# ESRMeter.net
KiCad netlist of a schematic drawn in EAGLE
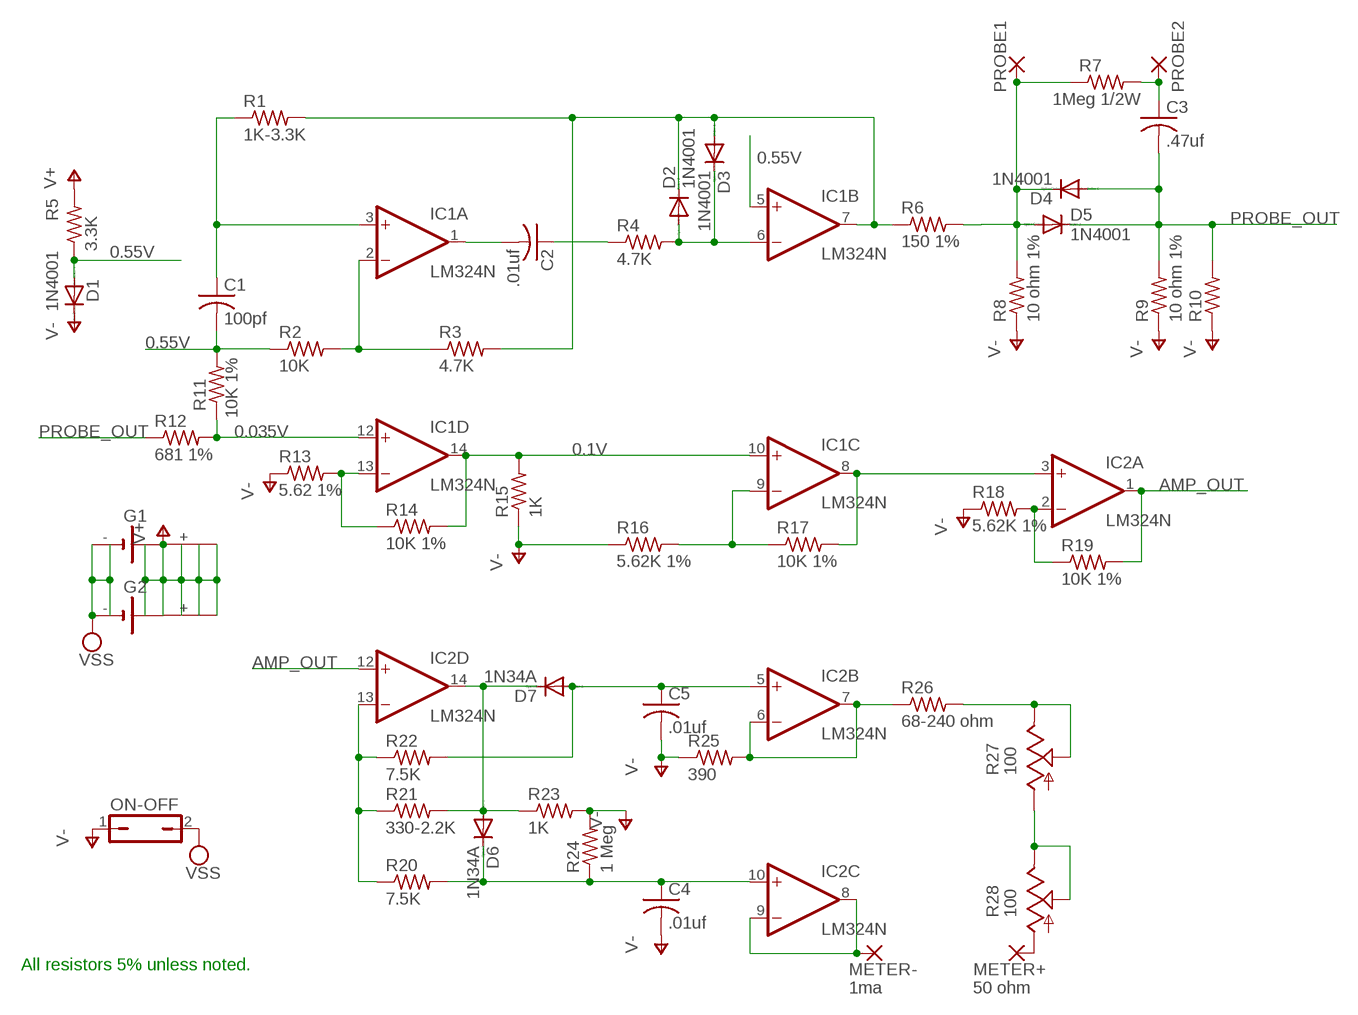
[diagram p0: schematic, sheet 1]

(export (version "E")
  (design (tool "Eeschema 10.0.6"))
  (components
    (comp (ref "C1")
      (value "100pf")
      (footprint "eagle-import:C050-025X075")
      (libsource (lib "eagle-import") (part "C-US050-025X075"))
    )
    (comp (ref "C2")
      (value ".01uf")
      (footprint "eagle-import:C050-025X075")
      (libsource (lib "eagle-import") (part "C-US050-025X075"))
    )
    (comp (ref "C3")
      (value ".47uf")
      (footprint "eagle-import:C075-052X106")
      (libsource (lib "eagle-import") (part "C-US075-052X106"))
    )
    (comp (ref "C4")
      (value ".01uf")
      (footprint "eagle-import:C050-025X075")
      (libsource (lib "eagle-import") (part "C-US050-025X075"))
    )
    (comp (ref "C5")
      (value ".01uf")
      (footprint "eagle-import:C050-025X075")
      (libsource (lib "eagle-import") (part "C-US050-025X075"))
    )
    (comp (ref "D1")
      (value "1N4001")
      (footprint "eagle-import:DO41-10")
      (libsource (lib "eagle-import") (part "1N4004"))
    )
    (comp (ref "D2")
      (value "1N4001")
      (footprint "eagle-import:DO41-10")
      (libsource (lib "eagle-import") (part "1N4004"))
    )
    (comp (ref "D3")
      (value "1N4001")
      (footprint "eagle-import:DO41-10")
      (libsource (lib "eagle-import") (part "1N4004"))
    )
    (comp (ref "D4")
      (value "1N4001")
      (footprint "eagle-import:DO41-10")
      (libsource (lib "eagle-import") (part "1N4004"))
    )
    (comp (ref "D5")
      (value "1N4001")
      (footprint "eagle-import:DO41-10")
      (libsource (lib "eagle-import") (part "1N4004"))
    )
    (comp (ref "D6")
      (value "1N34A")
      (footprint "eagle-import:DO41-10")
      (libsource (lib "eagle-import") (part "1N4004"))
    )
    (comp (ref "D7")
      (value "1N34A")
      (footprint "eagle-import:DO41-10")
      (libsource (lib "eagle-import") (part "1N4004"))
    )
    (comp (ref "G1")
      (value "B2430UNI")
      (footprint "eagle-import:B2430UNI")
      (libsource (lib "eagle-import") (part "B2430UNI"))
    )
    (comp (ref "G2")
      (value "B2430UNI")
      (footprint "eagle-import:B2430UNI")
      (libsource (lib "eagle-import") (part "B2430UNI"))
    )
    (comp (ref "IC1")
      (value "LM324N")
      (footprint "eagle-import:DIL14")
      (libsource (lib "eagle-import") (part "LM324N"))
    )
    (comp (ref "IC2")
      (value "LM324N")
      (footprint "eagle-import:DIL14")
      (libsource (lib "eagle-import") (part "LM324N"))
    )
    (comp (ref "METER+")
      (value "50 ohm")
      (footprint "eagle-import:2,15_1,0")
      (libsource (lib "eagle-import") (part "2,15/1,0"))
    )
    (comp (ref "METER-")
      (value "1ma")
      (footprint "eagle-import:2,15_1,0")
      (libsource (lib "eagle-import") (part "2,15/1,0"))
    )
    (comp (ref "ON-OFF")
      (value "JP1Q")
      (footprint "eagle-import:JP1")
      (libsource (lib "eagle-import") (part "JP1Q"))
    )
    (comp (ref "PROBE1")
      (value "2,15/1,0")
      (footprint "eagle-import:2,15_1,0")
      (libsource (lib "eagle-import") (part "2,15/1,0"))
    )
    (comp (ref "PROBE2")
      (value "2,15/1,0")
      (footprint "eagle-import:2,15_1,0")
      (libsource (lib "eagle-import") (part "2,15/1,0"))
    )
    (comp (ref "R1")
      (value "1K-3.3K")
      (footprint "eagle-import:0207_10")
      (libsource (lib "eagle-import") (part "R-US_0207/10"))
    )
    (comp (ref "R2")
      (value "10K")
      (footprint "eagle-import:0207_10")
      (libsource (lib "eagle-import") (part "R-US_0207/10"))
    )
    (comp (ref "R3")
      (value "4.7K")
      (footprint "eagle-import:0207_10")
      (libsource (lib "eagle-import") (part "R-US_0207/10"))
    )
    (comp (ref "R4")
      (value "4.7K")
      (footprint "eagle-import:0207_10")
      (libsource (lib "eagle-import") (part "R-US_0207/10"))
    )
    (comp (ref "R5")
      (value "3.3K")
      (footprint "eagle-import:0207_10")
      (libsource (lib "eagle-import") (part "R-US_0207/10"))
    )
    (comp (ref "R6")
      (value "150 1%")
      (footprint "eagle-import:0207_10")
      (libsource (lib "eagle-import") (part "R-US_0207/10"))
    )
    (comp (ref "R7")
      (value "1Meg 1/2W")
      (footprint "eagle-import:0207_12")
      (libsource (lib "eagle-import") (part "R-US_0207/12"))
    )
    (comp (ref "R8")
      (value "10 ohm 1%")
      (footprint "eagle-import:0207_10")
      (libsource (lib "eagle-import") (part "R-US_0207/10"))
    )
    (comp (ref "R9")
      (value "10 ohm 1%")
      (footprint "eagle-import:0207_10")
      (libsource (lib "eagle-import") (part "R-US_0207/10"))
    )
    (comp (ref "R10")
      (value "R-US_0207/10")
      (footprint "eagle-import:0207_10")
      (libsource (lib "eagle-import") (part "R-US_0207/10"))
    )
    (comp (ref "R11")
      (value "10K 1%")
      (footprint "eagle-import:0207_10")
      (libsource (lib "eagle-import") (part "R-US_0207/10"))
    )
    (comp (ref "R12")
      (value "681 1%")
      (footprint "eagle-import:0207_10")
      (libsource (lib "eagle-import") (part "R-US_0207/10"))
    )
    (comp (ref "R13")
      (value "5.62 1%")
      (footprint "eagle-import:0207_10")
      (libsource (lib "eagle-import") (part "R-US_0207/10"))
    )
    (comp (ref "R14")
      (value "10K 1%")
      (footprint "eagle-import:0207_10")
      (libsource (lib "eagle-import") (part "R-US_0207/10"))
    )
    (comp (ref "R15")
      (value "1K")
      (footprint "eagle-import:0207_10")
      (libsource (lib "eagle-import") (part "R-US_0207/10"))
    )
    (comp (ref "R16")
      (value "5.62K 1%")
      (footprint "eagle-import:0207_10")
      (libsource (lib "eagle-import") (part "R-US_0207/10"))
    )
    (comp (ref "R17")
      (value "10K 1%")
      (footprint "eagle-import:0207_10")
      (libsource (lib "eagle-import") (part "R-US_0207/10"))
    )
    (comp (ref "R18")
      (value "5.62K 1%")
      (footprint "eagle-import:0207_10")
      (libsource (lib "eagle-import") (part "R-US_0207/10"))
    )
    (comp (ref "R19")
      (value "10K 1%")
      (footprint "eagle-import:0207_10")
      (libsource (lib "eagle-import") (part "R-US_0207/10"))
    )
    (comp (ref "R20")
      (value "7.5K")
      (footprint "eagle-import:0207_10")
      (libsource (lib "eagle-import") (part "R-US_0207/10"))
    )
    (comp (ref "R21")
      (value "330-2.2K")
      (footprint "eagle-import:0207_10")
      (libsource (lib "eagle-import") (part "R-US_0207/10"))
    )
    (comp (ref "R22")
      (value "7.5K")
      (footprint "eagle-import:0207_10")
      (libsource (lib "eagle-import") (part "R-US_0207/10"))
    )
    (comp (ref "R23")
      (value "1K")
      (footprint "eagle-import:0207_10")
      (libsource (lib "eagle-import") (part "R-US_0207/10"))
    )
    (comp (ref "R24")
      (value "1 Meg")
      (footprint "eagle-import:0207_12")
      (libsource (lib "eagle-import") (part "R-US_0207/12"))
    )
    (comp (ref "R25")
      (value "390")
      (footprint "eagle-import:0207_10")
      (libsource (lib "eagle-import") (part "R-US_0207/10"))
    )
    (comp (ref "R26")
      (value "68-240 ohm")
      (footprint "eagle-import:0207_10")
      (libsource (lib "eagle-import") (part "R-US_0207/10"))
    )
    (comp (ref "R27")
      (value "100")
      (footprint "eagle-import:B64W")
      (libsource (lib "eagle-import") (part "TRIM_US-B64W"))
    )
    (comp (ref "R28")
      (value "100")
      (footprint "eagle-import:B64W")
      (libsource (lib "eagle-import") (part "TRIM_US-B64W"))
    )
  )
  (nets
    (net (code "1") (name "/0.1V") (class "Default")
      (node (ref "IC1") (pin "10") (pinfunction "+IN_10") (pintype "input"))
      (node (ref "IC1") (pin "14") (pinfunction "OUT_14") (pintype "output"))
      (node (ref "R14") (pin "2") (pinfunction "2_2") (pintype "passive"))
      (node (ref "R15") (pin "2") (pinfunction "2_2") (pintype "passive"))
    )
    (net (code "2") (name "/0.035V") (class "Default")
      (node (ref "IC1") (pin "12") (pinfunction "+IN_12") (pintype "input"))
      (node (ref "R11") (pin "1") (pinfunction "1_1") (pintype "passive"))
      (node (ref "R12") (pin "2") (pinfunction "2_2") (pintype "passive"))
    )
    (net (code "3") (name "/0.55V") (class "Default")
      (node (ref "C1") (pin "2") (pinfunction "2_2") (pintype "passive"))
      (node (ref "D1") (pin "A") (pinfunction "A_A") (pintype "passive"))
      (node (ref "IC1") (pin "5") (pinfunction "+IN_5") (pintype "input"))
      (node (ref "R11") (pin "2") (pinfunction "2_2") (pintype "passive"))
      (node (ref "R2") (pin "1") (pinfunction "1_1") (pintype "passive"))
      (node (ref "R5") (pin "1") (pinfunction "1_1") (pintype "passive"))
    )
    (net (code "4") (name "/AMP_OUT") (class "Default")
      (node (ref "IC2") (pin "1") (pinfunction "OUT_1") (pintype "output"))
      (node (ref "IC2") (pin "12") (pinfunction "+IN_12") (pintype "input"))
      (node (ref "R19") (pin "2") (pinfunction "2_2") (pintype "passive"))
    )
    (net (code "5") (name "/PROBE_OUT") (class "Default")
      (node (ref "C3") (pin "2") (pinfunction "2_2") (pintype "passive"))
      (node (ref "D4") (pin "A") (pinfunction "A_A") (pintype "passive"))
      (node (ref "D5") (pin "C") (pinfunction "C_C") (pintype "passive"))
      (node (ref "R10") (pin "2") (pinfunction "2_2") (pintype "passive"))
      (node (ref "R12") (pin "1") (pinfunction "1_1") (pintype "passive"))
      (node (ref "R9") (pin "2") (pinfunction "2_2") (pintype "passive"))
    )
    (net (code "6") (name "Net-(C2-Pad1)") (class "Default")
      (node (ref "C2") (pin "1") (pinfunction "1_1") (pintype "passive"))
      (node (ref "R4") (pin "1") (pinfunction "1_1") (pintype "passive"))
    )
    (net (code "7") (name "Net-(IC1A-+IN)") (class "Default")
      (node (ref "C1") (pin "1") (pinfunction "1_1") (pintype "passive"))
      (node (ref "IC1") (pin "3") (pinfunction "+IN_3") (pintype "input"))
      (node (ref "R1") (pin "1") (pinfunction "1_1") (pintype "passive"))
    )
    (net (code "8") (name "Net-(IC1A--IN)") (class "Default")
      (node (ref "IC1") (pin "2") (pinfunction "-IN_2") (pintype "input"))
      (node (ref "R2") (pin "2") (pinfunction "2_2") (pintype "passive"))
      (node (ref "R3") (pin "1") (pinfunction "1_1") (pintype "passive"))
    )
    (net (code "9") (name "Net-(IC1A-OUT)") (class "Default")
      (node (ref "C2") (pin "2") (pinfunction "2_2") (pintype "passive"))
      (node (ref "IC1") (pin "1") (pinfunction "OUT_1") (pintype "output"))
    )
    (net (code "10") (name "Net-(IC1B--IN)") (class "Default")
      (node (ref "D2") (pin "A") (pinfunction "A_A") (pintype "passive"))
      (node (ref "D3") (pin "C") (pinfunction "C_C") (pintype "passive"))
      (node (ref "IC1") (pin "6") (pinfunction "-IN_6") (pintype "input"))
      (node (ref "R4") (pin "2") (pinfunction "2_2") (pintype "passive"))
    )
    (net (code "11") (name "Net-(IC1B-OUT)") (class "Default")
      (node (ref "D2") (pin "C") (pinfunction "C_C") (pintype "passive"))
      (node (ref "D3") (pin "A") (pinfunction "A_A") (pintype "passive"))
      (node (ref "IC1") (pin "7") (pinfunction "OUT_7") (pintype "output"))
      (node (ref "R1") (pin "2") (pinfunction "2_2") (pintype "passive"))
      (node (ref "R3") (pin "2") (pinfunction "2_2") (pintype "passive"))
      (node (ref "R6") (pin "1") (pinfunction "1_1") (pintype "passive"))
    )
    (net (code "12") (name "Net-(IC1C--IN)") (class "Default")
      (node (ref "IC1") (pin "9") (pinfunction "-IN_9") (pintype "input"))
      (node (ref "R16") (pin "2") (pinfunction "2_2") (pintype "passive"))
      (node (ref "R17") (pin "1") (pinfunction "1_1") (pintype "passive"))
    )
    (net (code "13") (name "Net-(IC1C-OUT)") (class "Default")
      (node (ref "IC1") (pin "8") (pinfunction "OUT_8") (pintype "output"))
      (node (ref "IC2") (pin "3") (pinfunction "+IN_3") (pintype "input"))
      (node (ref "R17") (pin "2") (pinfunction "2_2") (pintype "passive"))
    )
    (net (code "14") (name "Net-(IC1D--IN)") (class "Default")
      (node (ref "IC1") (pin "13") (pinfunction "-IN_13") (pintype "input"))
      (node (ref "R13") (pin "2") (pinfunction "2_2") (pintype "passive"))
      (node (ref "R14") (pin "1") (pinfunction "1_1") (pintype "passive"))
    )
    (net (code "15") (name "Net-(IC2A--IN)") (class "Default")
      (node (ref "IC2") (pin "2") (pinfunction "-IN_2") (pintype "input"))
      (node (ref "R18") (pin "2") (pinfunction "2_2") (pintype "passive"))
      (node (ref "R19") (pin "1") (pinfunction "1_1") (pintype "passive"))
    )
    (net (code "16") (name "Net-(IC2B-+IN)") (class "Default")
      (node (ref "C5") (pin "1") (pinfunction "1_1") (pintype "passive"))
      (node (ref "D7") (pin "A") (pinfunction "A_A") (pintype "passive"))
      (node (ref "IC2") (pin "5") (pinfunction "+IN_5") (pintype "input"))
      (node (ref "R22") (pin "2") (pinfunction "2_2") (pintype "passive"))
    )
    (net (code "17") (name "Net-(IC2B--IN)") (class "Default")
      (node (ref "IC2") (pin "6") (pinfunction "-IN_6") (pintype "input"))
      (node (ref "IC2") (pin "7") (pinfunction "OUT_7") (pintype "output"))
      (node (ref "R25") (pin "2") (pinfunction "2_2") (pintype "passive"))
      (node (ref "R26") (pin "1") (pinfunction "1_1") (pintype "passive"))
    )
    (net (code "18") (name "Net-(IC2C-+IN)") (class "Default")
      (node (ref "C4") (pin "1") (pinfunction "1_1") (pintype "passive"))
      (node (ref "D6") (pin "C") (pinfunction "C_C") (pintype "passive"))
      (node (ref "IC2") (pin "10") (pinfunction "+IN_10") (pintype "input"))
      (node (ref "R20") (pin "2") (pinfunction "2_2") (pintype "passive"))
      (node (ref "R24") (pin "1") (pinfunction "1_1") (pintype "passive"))
    )
    (net (code "19") (name "Net-(IC2C--IN)") (class "Default")
      (node (ref "IC2") (pin "8") (pinfunction "OUT_8") (pintype "output"))
      (node (ref "IC2") (pin "9") (pinfunction "-IN_9") (pintype "input"))
      (node (ref "METER-") (pin "1") (pinfunction "P_1") (pintype "passive"))
    )
    (net (code "20") (name "Net-(IC2D--IN)") (class "Default")
      (node (ref "IC2") (pin "13") (pinfunction "-IN_13") (pintype "input"))
      (node (ref "R20") (pin "1") (pinfunction "1_1") (pintype "passive"))
      (node (ref "R21") (pin "1") (pinfunction "1_1") (pintype "passive"))
      (node (ref "R22") (pin "1") (pinfunction "1_1") (pintype "passive"))
    )
    (net (code "21") (name "Net-(IC2D-OUT)") (class "Default")
      (node (ref "D6") (pin "A") (pinfunction "A_A") (pintype "passive"))
      (node (ref "D7") (pin "C") (pinfunction "C_C") (pintype "passive"))
      (node (ref "IC2") (pin "14") (pinfunction "OUT_14") (pintype "output"))
      (node (ref "R21") (pin "2") (pinfunction "2_2") (pintype "passive"))
      (node (ref "R23") (pin "1") (pinfunction "1_1") (pintype "passive"))
    )
    (net (code "22") (name "Net-(METER+-P)") (class "Default")
      (node (ref "METER+") (pin "1") (pinfunction "P_1") (pintype "passive"))
      (node (ref "R28") (pin "A") (pinfunction "A_A") (pintype "passive"))
    )
    (net (code "23") (name "Net-(PROBE1-P)") (class "Default")
      (node (ref "D4") (pin "C") (pinfunction "C_C") (pintype "passive"))
      (node (ref "D5") (pin "A") (pinfunction "A_A") (pintype "passive"))
      (node (ref "PROBE1") (pin "1") (pinfunction "P_1") (pintype "passive"))
      (node (ref "R6") (pin "2") (pinfunction "2_2") (pintype "passive"))
      (node (ref "R7") (pin "1") (pinfunction "1_1") (pintype "passive"))
      (node (ref "R8") (pin "2") (pinfunction "2_2") (pintype "passive"))
    )
    (net (code "24") (name "Net-(PROBE2-P)") (class "Default")
      (node (ref "C3") (pin "1") (pinfunction "1_1") (pintype "passive"))
      (node (ref "PROBE2") (pin "1") (pinfunction "P_1") (pintype "passive"))
      (node (ref "R7") (pin "2") (pinfunction "2_2") (pintype "passive"))
    )
    (net (code "25") (name "Net-(R26-Pad2)") (class "Default")
      (node (ref "R26") (pin "2") (pinfunction "2_2") (pintype "passive"))
      (node (ref "R27") (pin "E") (pinfunction "E_E") (pintype "passive"))
      (node (ref "R27") (pin "S") (pinfunction "S_S") (pintype "passive"))
    )
    (net (code "26") (name "Net-(R27-PadA)") (class "Default")
      (node (ref "R27") (pin "A") (pinfunction "A_A") (pintype "passive"))
      (node (ref "R28") (pin "E") (pinfunction "E_E") (pintype "passive"))
      (node (ref "R28") (pin "S") (pinfunction "S_S") (pintype "passive"))
    )
    (net (code "27") (name "V+") (class "Default")
      (node (ref "G1") (pin "+") (pinfunction "+_+") (pintype "passive"))
      (node (ref "G1") (pin "+@1") (pinfunction "+_+@1") (pintype "passive"))
      (node (ref "G1") (pin "+@2") (pinfunction "+_+@2") (pintype "passive"))
      (node (ref "G1") (pin "+@3") (pinfunction "+_+@3") (pintype "passive"))
      (node (ref "G1") (pin "+@4") (pinfunction "+_+@4") (pintype "passive"))
      (node (ref "G2") (pin "+") (pinfunction "+_+") (pintype "passive"))
      (node (ref "G2") (pin "+@1") (pinfunction "+_+@1") (pintype "passive"))
      (node (ref "G2") (pin "+@2") (pinfunction "+_+@2") (pintype "passive"))
      (node (ref "G2") (pin "+@3") (pinfunction "+_+@3") (pintype "passive"))
      (node (ref "G2") (pin "+@4") (pinfunction "+_+@4") (pintype "passive"))
      (node (ref "R5") (pin "2") (pinfunction "2_2") (pintype "passive"))
    )
    (net (code "28") (name "V-") (class "Default")
      (node (ref "C4") (pin "2") (pinfunction "2_2") (pintype "passive"))
      (node (ref "C5") (pin "2") (pinfunction "2_2") (pintype "passive"))
      (node (ref "D1") (pin "C") (pinfunction "C_C") (pintype "passive"))
      (node (ref "ON-OFF") (pin "1") (pinfunction "1_1") (pintype "passive"))
      (node (ref "R10") (pin "1") (pinfunction "1_1") (pintype "passive"))
      (node (ref "R13") (pin "1") (pinfunction "1_1") (pintype "passive"))
      (node (ref "R15") (pin "1") (pinfunction "1_1") (pintype "passive"))
      (node (ref "R16") (pin "1") (pinfunction "1_1") (pintype "passive"))
      (node (ref "R18") (pin "1") (pinfunction "1_1") (pintype "passive"))
      (node (ref "R23") (pin "2") (pinfunction "2_2") (pintype "passive"))
      (node (ref "R24") (pin "2") (pinfunction "2_2") (pintype "passive"))
      (node (ref "R25") (pin "1") (pinfunction "1_1") (pintype "passive"))
      (node (ref "R8") (pin "1") (pinfunction "1_1") (pintype "passive"))
      (node (ref "R9") (pin "1") (pinfunction "1_1") (pintype "passive"))
    )
    (net (code "29") (name "VSS") (class "Default")
      (node (ref "G1") (pin "-") (pinfunction "-_-") (pintype "passive"))
      (node (ref "G1") (pin "-@1") (pinfunction "-_-@1") (pintype "passive"))
      (node (ref "G2") (pin "-") (pinfunction "-_-") (pintype "passive"))
      (node (ref "G2") (pin "-@1") (pinfunction "-_-@1") (pintype "passive"))
      (node (ref "ON-OFF") (pin "2") (pinfunction "2_2") (pintype "passive"))
    )
  )
)
